# LimitSwitches.net
KiCad netlist of a schematic drawn in EAGLE
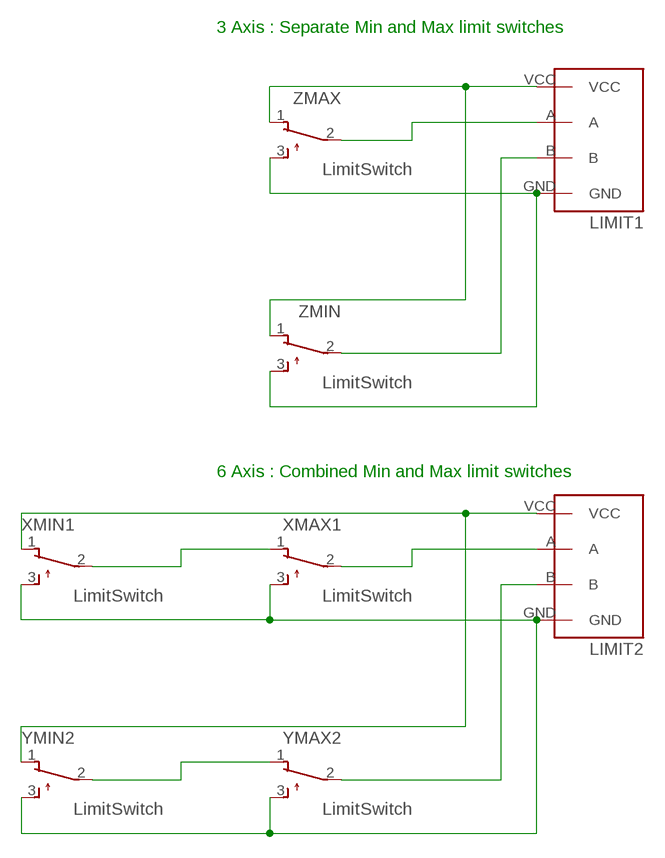
[diagram p0: schematic, sheet 1]

(export (version "E")
  (design (tool "Eeschema 10.0.6"))
  (components
    (comp (ref "LIMIT1")
      (value "CONN4B")
      (footprint "eagle-import:CONN4B")
      (libsource (lib "eagle-import") (part "CONN4B"))
    )
    (comp (ref "LIMIT2")
      (value "CONN4B")
      (footprint "eagle-import:CONN4B")
      (libsource (lib "eagle-import") (part "CONN4B"))
    )
    (comp (ref "XMAX1")
      (value "LimitSwitch")
      (footprint "eagle-import:TL3XPO")
      (libsource (lib "eagle-import") (part "TL32PO"))
    )
    (comp (ref "XMIN1")
      (value "LimitSwitch")
      (footprint "eagle-import:TL3XPO")
      (libsource (lib "eagle-import") (part "TL32PO"))
    )
    (comp (ref "YMAX2")
      (value "LimitSwitch")
      (footprint "eagle-import:TL3XPO")
      (libsource (lib "eagle-import") (part "TL32PO"))
    )
    (comp (ref "YMIN2")
      (value "LimitSwitch")
      (footprint "eagle-import:TL3XPO")
      (libsource (lib "eagle-import") (part "TL32PO"))
    )
    (comp (ref "ZMAX")
      (value "LimitSwitch")
      (footprint "eagle-import:TL3XPO")
      (libsource (lib "eagle-import") (part "TL32PO"))
    )
    (comp (ref "ZMIN")
      (value "LimitSwitch")
      (footprint "eagle-import:TL3XPO")
      (libsource (lib "eagle-import") (part "TL32PO"))
    )
  )
  (nets
    (net (code "1") (name "Net-(XMAX1-O)") (class "Default")
      (node (ref "XMAX1") (pin "1") (pinfunction "O_1") (pintype "passive"))
      (node (ref "XMIN1") (pin "2") (pinfunction "P_2") (pintype "passive"))
    )
    (net (code "2") (name "Net-(XMAX1-P)") (class "Default")
      (node (ref "LIMIT2") (pin "A") (pinfunction "A_A") (pintype "bidirectional"))
      (node (ref "XMAX1") (pin "2") (pinfunction "P_2") (pintype "passive"))
    )
    (net (code "3") (name "Net-(XMAX1-S)") (class "Default")
      (node (ref "LIMIT2") (pin "GND") (pinfunction "GND_GND") (pintype "power_in"))
      (node (ref "XMAX1") (pin "3") (pinfunction "S_3") (pintype "passive"))
      (node (ref "XMIN1") (pin "3") (pinfunction "S_3") (pintype "passive"))
      (node (ref "YMAX2") (pin "3") (pinfunction "S_3") (pintype "passive"))
      (node (ref "YMIN2") (pin "3") (pinfunction "S_3") (pintype "passive"))
    )
    (net (code "4") (name "Net-(XMIN1-O)") (class "Default")
      (node (ref "LIMIT2") (pin "VCC") (pinfunction "VCC_VCC") (pintype "power_in"))
      (node (ref "XMIN1") (pin "1") (pinfunction "O_1") (pintype "passive"))
      (node (ref "YMIN2") (pin "1") (pinfunction "O_1") (pintype "passive"))
    )
    (net (code "5") (name "Net-(YMAX2-O)") (class "Default")
      (node (ref "YMAX2") (pin "1") (pinfunction "O_1") (pintype "passive"))
      (node (ref "YMIN2") (pin "2") (pinfunction "P_2") (pintype "passive"))
    )
    (net (code "6") (name "Net-(YMAX2-P)") (class "Default")
      (node (ref "LIMIT2") (pin "B") (pinfunction "B_B") (pintype "bidirectional"))
      (node (ref "YMAX2") (pin "2") (pinfunction "P_2") (pintype "passive"))
    )
    (net (code "7") (name "Net-(ZMAX-O)") (class "Default")
      (node (ref "LIMIT1") (pin "VCC") (pinfunction "VCC_VCC") (pintype "power_in"))
      (node (ref "ZMAX") (pin "1") (pinfunction "O_1") (pintype "passive"))
      (node (ref "ZMIN") (pin "1") (pinfunction "O_1") (pintype "passive"))
    )
    (net (code "8") (name "Net-(ZMAX-P)") (class "Default")
      (node (ref "LIMIT1") (pin "A") (pinfunction "A_A") (pintype "bidirectional"))
      (node (ref "ZMAX") (pin "2") (pinfunction "P_2") (pintype "passive"))
    )
    (net (code "9") (name "Net-(ZMAX-S)") (class "Default")
      (node (ref "LIMIT1") (pin "GND") (pinfunction "GND_GND") (pintype "power_in"))
      (node (ref "ZMAX") (pin "3") (pinfunction "S_3") (pintype "passive"))
      (node (ref "ZMIN") (pin "3") (pinfunction "S_3") (pintype "passive"))
    )
    (net (code "10") (name "Net-(ZMIN-P)") (class "Default")
      (node (ref "LIMIT1") (pin "B") (pinfunction "B_B") (pintype "bidirectional"))
      (node (ref "ZMIN") (pin "2") (pinfunction "P_2") (pintype "passive"))
    )
  )
)
